# Schematic.net
KiCad netlist of a schematic drawn in Altium Designer
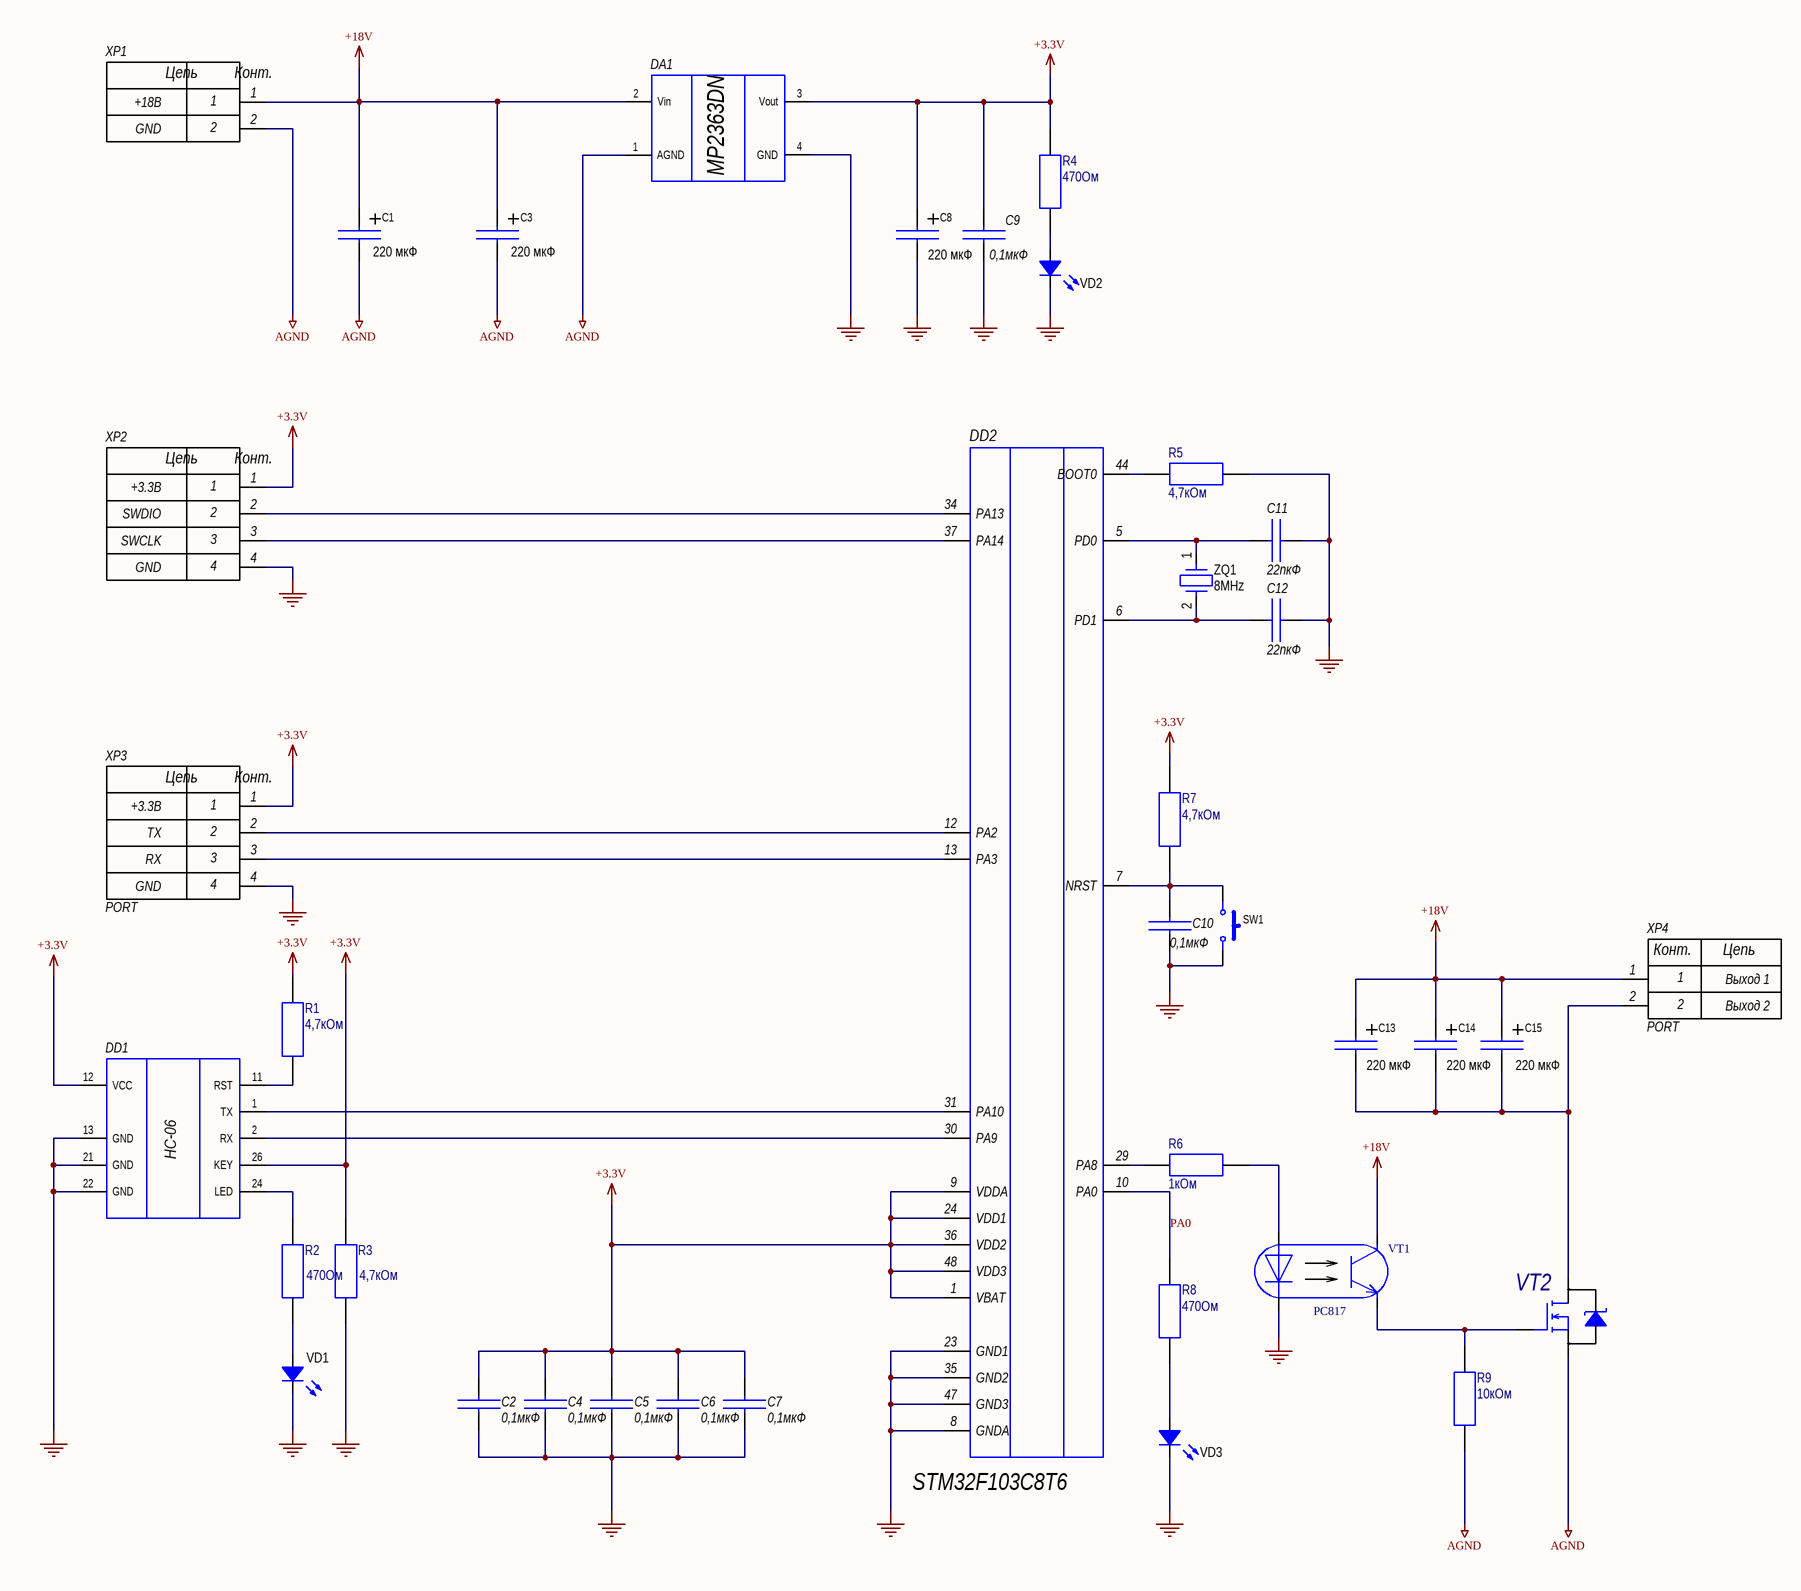
[diagram p0: Schematic.SchDoc]

(export (version "E")
  (design (tool "Eeschema 10.0.6"))
  (components
    (comp (ref "C1")
      (value "220 мкФ")
      (footprint "chip_25V_220uF")
      (fields (field (name "Comment") "220uF_25V_chip"))
      (libsource (lib "electrolytic") (part "220uF_25V_chip"))
    )
    (comp (ref "C2")
      (value "0,1мкФ")
      (footprint "CAP: SMD0805")
      (description "CAP")
      (fields (field (name "Comment") "SMD0805"))
      (libsource (lib "ceramic") (part "SMD0805"))
    )
    (comp (ref "C3")
      (value "220 мкФ")
      (footprint "chip_25V_220uF")
      (fields (field (name "Comment") "220uF_25V_chip"))
      (libsource (lib "electrolytic") (part "220uF_25V_chip"))
    )
    (comp (ref "C4")
      (value "0,1мкФ")
      (footprint "CAP: SMD0805")
      (description "CAP")
      (fields (field (name "Comment") "SMD0805"))
      (libsource (lib "ceramic") (part "SMD0805"))
    )
    (comp (ref "C5")
      (value "0,1мкФ")
      (footprint "CAP: SMD0805")
      (description "CAP")
      (fields (field (name "Comment") "SMD0805"))
      (libsource (lib "ceramic") (part "SMD0805"))
    )
    (comp (ref "C6")
      (value "0,1мкФ")
      (footprint "CAP: SMD0805")
      (description "CAP")
      (fields (field (name "Comment") "SMD0805"))
      (libsource (lib "ceramic") (part "SMD0805"))
    )
    (comp (ref "C7")
      (value "0,1мкФ")
      (footprint "CAP: SMD0805")
      (description "CAP")
      (fields (field (name "Comment") "SMD0805"))
      (libsource (lib "ceramic") (part "SMD0805"))
    )
    (comp (ref "C8")
      (value "220 мкФ")
      (footprint "chip_25V_220uF")
      (fields (field (name "Comment") "220uF_25V_chip"))
      (libsource (lib "electrolytic") (part "220uF_25V_chip"))
    )
    (comp (ref "C9")
      (value "0,1мкФ")
      (footprint "CAP: SMD0805")
      (description "CAP")
      (fields (field (name "Comment") "SMD0805"))
      (libsource (lib "ceramic") (part "SMD0805"))
    )
    (comp (ref "C10")
      (value "0,1мкФ")
      (footprint "CAP: SMD0805")
      (description "CAP")
      (fields (field (name "Comment") "SMD0805"))
      (libsource (lib "ceramic") (part "SMD0805"))
    )
    (comp (ref "C11")
      (value "22пкФ")
      (footprint "CAP: SMD0805")
      (description "CAP")
      (fields (field (name "Comment") "SMD0805"))
      (libsource (lib "ceramic") (part "SMD0805"))
    )
    (comp (ref "C12")
      (value "22пкФ")
      (footprint "CAP: SMD0805")
      (description "CAP")
      (fields (field (name "Comment") "SMD0805"))
      (libsource (lib "ceramic") (part "SMD0805"))
    )
    (comp (ref "C13")
      (value "220 мкФ")
      (footprint "chip_25V_220uF")
      (fields (field (name "Comment") "220uF_25V_chip"))
      (libsource (lib "electrolytic") (part "220uF_25V_chip"))
    )
    (comp (ref "C14")
      (value "220 мкФ")
      (footprint "chip_25V_220uF")
      (fields (field (name "Comment") "220uF_25V_chip"))
      (libsource (lib "electrolytic") (part "220uF_25V_chip"))
    )
    (comp (ref "C15")
      (value "220 мкФ")
      (footprint "chip_25V_220uF")
      (fields (field (name "Comment") "220uF_25V_chip"))
      (libsource (lib "electrolytic") (part "220uF_25V_chip"))
    )
    (comp (ref "DA1")
      (value "MP2363DN")
      (footprint "MP2363DN")
      (description "Преобразователь напряжения")
      (libsource (lib "Schlib1") (part "MP2363DN"))
    )
    (comp (ref "DD1") (value "HC-06") (footprint "HC-06") (libsource (lib "Schlib1") (part "HC-06")))
    (comp (ref "DD2")
      (value "STM32F103C8T6")
      (footprint "LQFP48_N")
      (libsource (lib "stm32f10x_gost") (part "STM32F103C8T6(Dinara)"))
    )
    (comp (ref "R1")
      (value "4,7кОм")
      (footprint "RES: SMD0805")
      (libsource (lib "resistors") (part "SMD0805"))
    )
    (comp (ref "R2")
      (value "470Ом")
      (footprint "RES: SMD0805")
      (libsource (lib "resistors") (part "SMD0805"))
    )
    (comp (ref "R3")
      (value "4,7кОм")
      (footprint "RES: SMD0805")
      (libsource (lib "resistors") (part "SMD0805"))
    )
    (comp (ref "R4")
      (value "470Ом")
      (footprint "RES: SMD0805")
      (libsource (lib "resistors") (part "SMD0805"))
    )
    (comp (ref "R5")
      (value "4,7кОм")
      (footprint "RES: SMD0805")
      (libsource (lib "resistors") (part "SMD0805"))
    )
    (comp (ref "R6") (value "1кОм") (footprint "RES: SMD0805") (libsource (lib "resistors") (part "SMD0805")))
    (comp (ref "R7")
      (value "4,7кОм")
      (footprint "RES: SMD0805")
      (libsource (lib "resistors") (part "SMD0805"))
    )
    (comp (ref "R8")
      (value "470Ом")
      (footprint "RES: SMD0805")
      (libsource (lib "resistors") (part "SMD0805"))
    )
    (comp (ref "R9")
      (value "10кОм")
      (footprint "RES: SMD0805")
      (libsource (lib "resistors") (part "SMD0805"))
    )
    (comp (ref "SW1") (value "SWITCH") (footprint "KLS76x6x4.3") (libsource (lib "Schlib1") (part "SWITCH")))
    (comp (ref "VD1") (value "RED") (footprint "LED0805") (libsource (lib "Schlib1") (part "diode_led")))
    (comp (ref "VD2") (value "RED") (footprint "LED0805") (libsource (lib "Schlib1") (part "diode_led")))
    (comp (ref "VD3") (value "RED") (footprint "LED0805") (libsource (lib "Schlib1") (part "diode_led")))
    (comp (ref "VT1") (value "PC817") (footprint "DIP4_SMD_PC817") (libsource (lib "Schlib1") (part "PC817")))
    (comp (ref "VT2")
      (value "IRF540")
      (footprint "IRF540_D2Pak")
      (fields (field (name "PUBLISHER") "Andrew Danich"))
      (libsource (lib "Schlib1") (part "IRF540"))
    )
    (comp (ref "XP1") (value "PORT") (footprint "DJK-02A") (libsource (lib "Schlib1") (part "PH2.0-2P_XS1")))
    (comp (ref "XP2") (value "PORT") (footprint "ph2.0-4P") (libsource (lib "Schlib1") (part "PH2.0-4P_XP1")))
    (comp (ref "XP3") (value "PORT") (footprint "ph2.0-4P") (libsource (lib "Schlib1") (part "PH2.0-4P_XP2")))
    (comp (ref "XP4") (value "PORT") (footprint "DJK-02A") (libsource (lib "Schlib1") (part "PH2.0-2P_XS2")))
    (comp (ref "ZQ1") (value "8MHz") (footprint "HC-49SM") (libsource (lib "Schlib1") (part "HC-49")))
  )
  (nets
    (net (code "1") (name "+3.3V") (class "Default")
      (node (ref "C2") (pin "2") (pinfunction "2_2") (pintype "passive"))
      (node (ref "C4") (pin "2") (pinfunction "2_2") (pintype "passive"))
      (node (ref "C5") (pin "2") (pinfunction "2_2") (pintype "passive"))
      (node (ref "C6") (pin "2") (pinfunction "2_2") (pintype "passive"))
      (node (ref "C7") (pin "2") (pinfunction "2_2") (pintype "passive"))
      (node (ref "C8") (pin "1") (pinfunction "1_1") (pintype "passive"))
      (node (ref "C9") (pin "2") (pinfunction "2_2") (pintype "passive"))
      (node (ref "DA1") (pin "3") (pinfunction "Vout_3") (pintype "passive"))
      (node (ref "DD1") (pin "12") (pinfunction "VCC_12") (pintype "passive"))
      (node (ref "DD1") (pin "26") (pinfunction "KEY_26") (pintype "passive"))
      (node (ref "DD2") (pin "1") (pinfunction "VBAT_1") (pintype "passive"))
      (node (ref "DD2") (pin "24") (pinfunction "VDD1_24") (pintype "passive"))
      (node (ref "DD2") (pin "36") (pinfunction "VDD2_36") (pintype "passive"))
      (node (ref "DD2") (pin "48") (pinfunction "VDD3_48") (pintype "passive"))
      (node (ref "DD2") (pin "9") (pinfunction "VDDA_9") (pintype "passive"))
      (node (ref "R1") (pin "2") (pinfunction "2_2") (pintype "passive"))
      (node (ref "R3") (pin "2") (pinfunction "2_2") (pintype "passive"))
      (node (ref "R4") (pin "2") (pinfunction "2_2") (pintype "passive"))
      (node (ref "R7") (pin "2") (pinfunction "2_2") (pintype "passive"))
      (node (ref "XP2") (pin "1") (pinfunction "+3.3B_1") (pintype "passive"))
      (node (ref "XP3") (pin "1") (pinfunction "+3.3B_1") (pintype "passive"))
    )
    (net (code "2") (name "+18V") (class "Default")
      (node (ref "C1") (pin "1") (pinfunction "1_1") (pintype "passive"))
      (node (ref "C13") (pin "1") (pinfunction "1_1") (pintype "passive"))
      (node (ref "C14") (pin "1") (pinfunction "1_1") (pintype "passive"))
      (node (ref "C15") (pin "1") (pinfunction "1_1") (pintype "passive"))
      (node (ref "C3") (pin "1") (pinfunction "1_1") (pintype "passive"))
      (node (ref "DA1") (pin "2") (pinfunction "Vin_2") (pintype "passive"))
      (node (ref "VT1") (pin "4") (pinfunction "К_4") (pintype "passive"))
      (node (ref "XP1") (pin "1") (pinfunction "+18B_1") (pintype "passive"))
      (node (ref "XP4") (pin "1") (pinfunction "Выход_1_1") (pintype "passive"))
    )
    (net (code "3") (name "/PA0") (class "Default")
      (node (ref "DD2") (pin "10") (pinfunction "PA0_10") (pintype "passive"))
      (node (ref "R8") (pin "2") (pinfunction "2_2") (pintype "passive"))
    )
    (net (code "4") (name "AGND") (class "Default")
      (node (ref "C1") (pin "2") (pinfunction "2_2") (pintype "passive"))
      (node (ref "C3") (pin "2") (pinfunction "2_2") (pintype "passive"))
      (node (ref "DA1") (pin "1") (pinfunction "AGND_1") (pintype "passive"))
      (node (ref "R9") (pin "1") (pinfunction "1_1") (pintype "passive"))
      (node (ref "VT2") (pin "3") (pinfunction "S_3") (pintype "passive"))
      (node (ref "XP1") (pin "2") (pinfunction "GND_2") (pintype "passive"))
    )
    (net (code "5") (name "GND") (class "Default")
      (node (ref "C10") (pin "1") (pinfunction "1_1") (pintype "passive"))
      (node (ref "C11") (pin "2") (pinfunction "2_2") (pintype "passive"))
      (node (ref "C12") (pin "2") (pinfunction "2_2") (pintype "passive"))
      (node (ref "C2") (pin "1") (pinfunction "1_1") (pintype "passive"))
      (node (ref "C4") (pin "1") (pinfunction "1_1") (pintype "passive"))
      (node (ref "C5") (pin "1") (pinfunction "1_1") (pintype "passive"))
      (node (ref "C6") (pin "1") (pinfunction "1_1") (pintype "passive"))
      (node (ref "C7") (pin "1") (pinfunction "1_1") (pintype "passive"))
      (node (ref "C8") (pin "2") (pinfunction "2_2") (pintype "passive"))
      (node (ref "C9") (pin "1") (pinfunction "1_1") (pintype "passive"))
      (node (ref "DA1") (pin "4") (pinfunction "GND_4") (pintype "passive"))
      (node (ref "DD1") (pin "13") (pinfunction "GND_13") (pintype "passive"))
      (node (ref "DD1") (pin "21") (pinfunction "GND_21") (pintype "passive"))
      (node (ref "DD1") (pin "22") (pinfunction "GND_22") (pintype "passive"))
      (node (ref "DD2") (pin "23") (pinfunction "GND1_23") (pintype "passive"))
      (node (ref "DD2") (pin "35") (pinfunction "GND2_35") (pintype "passive"))
      (node (ref "DD2") (pin "47") (pinfunction "GND3_47") (pintype "passive"))
      (node (ref "DD2") (pin "8") (pinfunction "GNDA_8") (pintype "passive"))
      (node (ref "R3") (pin "1") (pinfunction "1_1") (pintype "passive"))
      (node (ref "R5") (pin "2") (pinfunction "2_2") (pintype "passive"))
      (node (ref "SW1") (pin "2") (pinfunction "2_2") (pintype "passive"))
      (node (ref "VD1") (pin "2") (pinfunction "K_2") (pintype "passive"))
      (node (ref "VD2") (pin "2") (pinfunction "K_2") (pintype "passive"))
      (node (ref "VD3") (pin "2") (pinfunction "K_2") (pintype "passive"))
      (node (ref "VT1") (pin "2") (pinfunction "K_2") (pintype "passive"))
      (node (ref "XP2") (pin "4") (pinfunction "GND_4") (pintype "passive"))
      (node (ref "XP3") (pin "4") (pinfunction "GND_4") (pintype "passive"))
    )
    (net (code "6") (name "Net-(DD1-LED)") (class "Default")
      (node (ref "DD1") (pin "24") (pinfunction "LED_24") (pintype "passive"))
      (node (ref "R2") (pin "2") (pinfunction "2_2") (pintype "passive"))
    )
    (net (code "7") (name "Net-(DD1-RST)") (class "Default")
      (node (ref "DD1") (pin "11") (pinfunction "RST_11") (pintype "passive"))
      (node (ref "R1") (pin "1") (pinfunction "1_1") (pintype "passive"))
    )
    (net (code "8") (name "Net-(DD1-RX)") (class "Default")
      (node (ref "DD1") (pin "2") (pinfunction "RX_2") (pintype "passive"))
      (node (ref "DD2") (pin "30") (pinfunction "PA9_30") (pintype "passive"))
    )
    (net (code "9") (name "Net-(DD1-TX)") (class "Default")
      (node (ref "DD1") (pin "1") (pinfunction "TX_1") (pintype "passive"))
      (node (ref "DD2") (pin "31") (pinfunction "PA10_31") (pintype "passive"))
    )
    (net (code "10") (name "Net-(DD2-BOOT0)") (class "Default")
      (node (ref "DD2") (pin "44") (pinfunction "BOOT0_44") (pintype "passive"))
      (node (ref "R5") (pin "1") (pinfunction "1_1") (pintype "passive"))
    )
    (net (code "11") (name "Net-(DD2-NRST)") (class "Default")
      (node (ref "C10") (pin "2") (pinfunction "2_2") (pintype "passive"))
      (node (ref "DD2") (pin "7") (pinfunction "NRST_7") (pintype "passive"))
      (node (ref "R7") (pin "1") (pinfunction "1_1") (pintype "passive"))
      (node (ref "SW1") (pin "1") (pinfunction "1_1") (pintype "passive"))
    )
    (net (code "12") (name "Net-(DD2-PA2)") (class "Default")
      (node (ref "DD2") (pin "12") (pinfunction "PA2_12") (pintype "passive"))
      (node (ref "XP3") (pin "2") (pinfunction "TX_2") (pintype "passive"))
    )
    (net (code "13") (name "Net-(DD2-PA3)") (class "Default")
      (node (ref "DD2") (pin "13") (pinfunction "PA3_13") (pintype "passive"))
      (node (ref "XP3") (pin "3") (pinfunction "RX_3") (pintype "passive"))
    )
    (net (code "14") (name "Net-(DD2-PA8)") (class "Default")
      (node (ref "DD2") (pin "29") (pinfunction "PA8_29") (pintype "passive"))
      (node (ref "R6") (pin "2") (pinfunction "2_2") (pintype "passive"))
    )
    (net (code "15") (name "Net-(DD2-PA13)") (class "Default")
      (node (ref "DD2") (pin "34") (pinfunction "PA13_34") (pintype "passive"))
      (node (ref "XP2") (pin "2") (pinfunction "SWDIO_2") (pintype "passive"))
    )
    (net (code "16") (name "Net-(DD2-PA14)") (class "Default")
      (node (ref "DD2") (pin "37") (pinfunction "PA14_37") (pintype "passive"))
      (node (ref "XP2") (pin "3") (pinfunction "SWCLK_3") (pintype "passive"))
    )
    (net (code "17") (name "Net-(DD2-PD0)") (class "Default")
      (node (ref "C11") (pin "1") (pinfunction "1_1") (pintype "passive"))
      (node (ref "DD2") (pin "5") (pinfunction "PD0_5") (pintype "passive"))
      (node (ref "ZQ1") (pin "1") (pinfunction "1_1") (pintype "passive"))
    )
    (net (code "18") (name "Net-(DD2-PD1)") (class "Default")
      (node (ref "C12") (pin "1") (pinfunction "1_1") (pintype "passive"))
      (node (ref "DD2") (pin "6") (pinfunction "PD1_6") (pintype "passive"))
      (node (ref "ZQ1") (pin "2") (pinfunction "2_2") (pintype "passive"))
    )
    (net (code "19") (name "Net-(VD1-A)") (class "Default")
      (node (ref "R2") (pin "1") (pinfunction "1_1") (pintype "passive"))
      (node (ref "VD1") (pin "1") (pinfunction "A_1") (pintype "passive"))
    )
    (net (code "20") (name "Net-(VD2-A)") (class "Default")
      (node (ref "R4") (pin "1") (pinfunction "1_1") (pintype "passive"))
      (node (ref "VD2") (pin "1") (pinfunction "A_1") (pintype "passive"))
    )
    (net (code "21") (name "Net-(VD3-A)") (class "Default")
      (node (ref "R8") (pin "1") (pinfunction "1_1") (pintype "passive"))
      (node (ref "VD3") (pin "1") (pinfunction "A_1") (pintype "passive"))
    )
    (net (code "22") (name "Net-(VT1-A)") (class "Default")
      (node (ref "R6") (pin "1") (pinfunction "1_1") (pintype "passive"))
      (node (ref "VT1") (pin "1") (pinfunction "A_1") (pintype "passive"))
    )
    (net (code "23") (name "Net-(VT1-Э)") (class "Default")
      (node (ref "R9") (pin "2") (pinfunction "2_2") (pintype "passive"))
      (node (ref "VT1") (pin "3") (pinfunction "Э_3") (pintype "passive"))
      (node (ref "VT2") (pin "1") (pinfunction "G_1") (pintype "passive"))
    )
    (net (code "24") (name "Net-(VT2-D)") (class "Default")
      (node (ref "C13") (pin "2") (pinfunction "2_2") (pintype "passive"))
      (node (ref "C14") (pin "2") (pinfunction "2_2") (pintype "passive"))
      (node (ref "C15") (pin "2") (pinfunction "2_2") (pintype "passive"))
      (node (ref "VT2") (pin "2") (pinfunction "D_2") (pintype "passive"))
      (node (ref "XP4") (pin "2") (pinfunction "Выход_2_2") (pintype "passive"))
    )
  )
)
